# Circular_LED_v0_9b.net
KiCad netlist of a schematic drawn in EAGLE
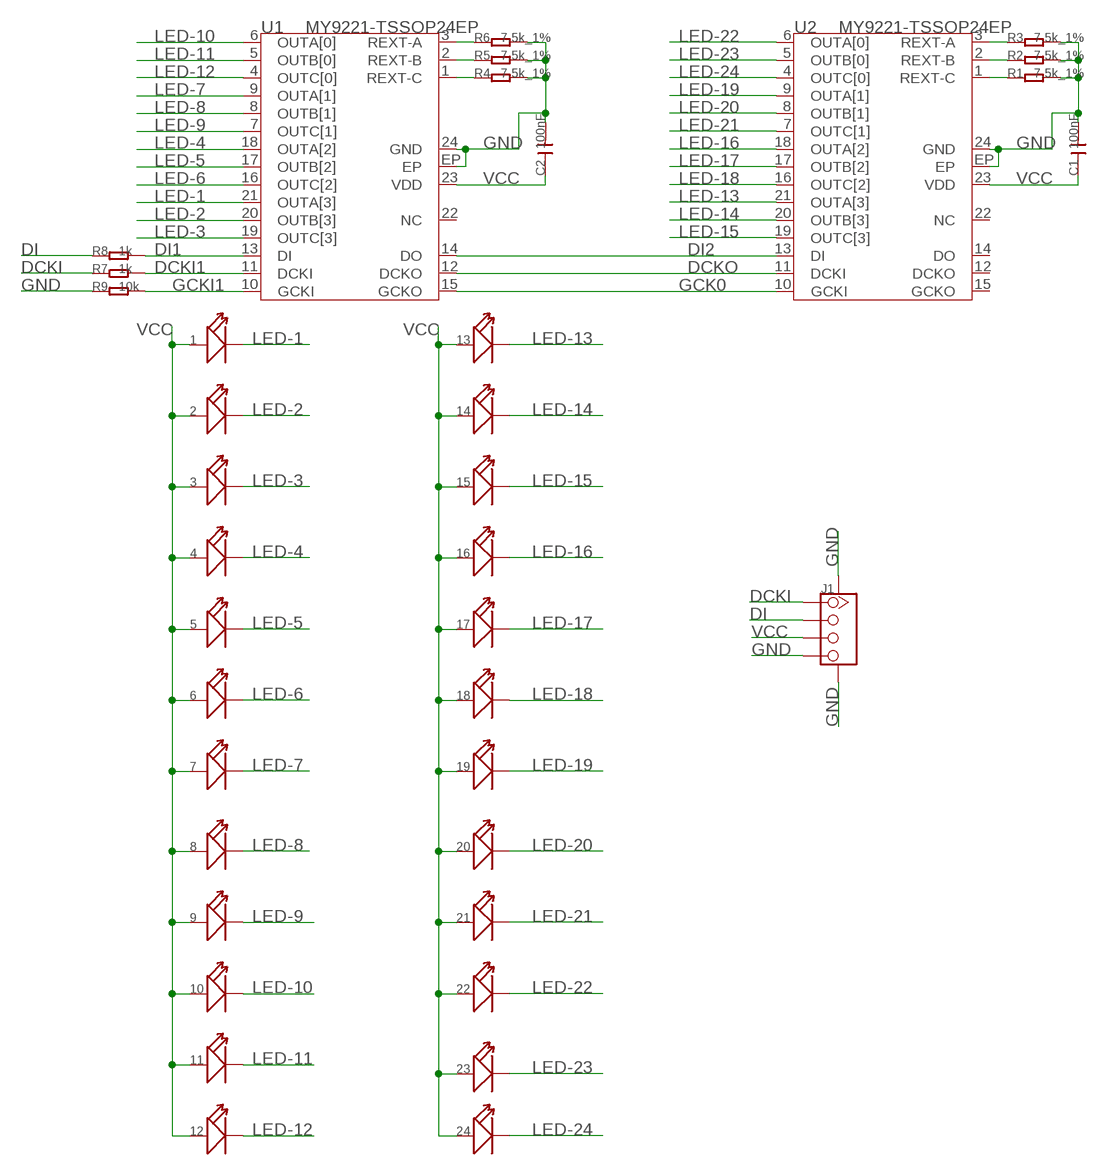
[diagram p0: schematic, sheet 1]

(export (version "E")
  (design (tool "Eeschema 10.0.6"))
  (components
    (comp (ref "1")
      (value "LED'1206'")
      (footprint "eagle-import:LED-1206")
      (libsource (lib "eagle-import") (part "LED'1206'"))
    )
    (comp (ref "2")
      (value "LED'1206'")
      (footprint "eagle-import:LED-1206")
      (libsource (lib "eagle-import") (part "LED'1206'"))
    )
    (comp (ref "3")
      (value "LED'1206'")
      (footprint "eagle-import:LED-1206")
      (libsource (lib "eagle-import") (part "LED'1206'"))
    )
    (comp (ref "4")
      (value "LED'1206'")
      (footprint "eagle-import:LED-1206")
      (libsource (lib "eagle-import") (part "LED'1206'"))
    )
    (comp (ref "5")
      (value "LED'1206'")
      (footprint "eagle-import:LED-1206")
      (libsource (lib "eagle-import") (part "LED'1206'"))
    )
    (comp (ref "6")
      (value "LED'1206'")
      (footprint "eagle-import:LED-1206")
      (libsource (lib "eagle-import") (part "LED'1206'"))
    )
    (comp (ref "7")
      (value "LED'1206'")
      (footprint "eagle-import:LED-1206")
      (libsource (lib "eagle-import") (part "LED'1206'"))
    )
    (comp (ref "8")
      (value "LED'1206'")
      (footprint "eagle-import:LED-1206")
      (libsource (lib "eagle-import") (part "LED'1206'"))
    )
    (comp (ref "9")
      (value "LED'1206'")
      (footprint "eagle-import:LED-1206")
      (libsource (lib "eagle-import") (part "LED'1206'"))
    )
    (comp (ref "10")
      (value "LED'1206'")
      (footprint "eagle-import:LED-1206")
      (libsource (lib "eagle-import") (part "LED'1206'"))
    )
    (comp (ref "11")
      (value "LED'1206'")
      (footprint "eagle-import:LED-1206")
      (libsource (lib "eagle-import") (part "LED'1206'"))
    )
    (comp (ref "12")
      (value "LED'1206'")
      (footprint "eagle-import:LED-1206")
      (libsource (lib "eagle-import") (part "LED'1206'"))
    )
    (comp (ref "13")
      (value "LED'1206'")
      (footprint "eagle-import:LED-1206")
      (libsource (lib "eagle-import") (part "LED'1206'"))
    )
    (comp (ref "14")
      (value "LED'1206'")
      (footprint "eagle-import:LED-1206")
      (libsource (lib "eagle-import") (part "LED'1206'"))
    )
    (comp (ref "15")
      (value "LED'1206'")
      (footprint "eagle-import:LED-1206")
      (libsource (lib "eagle-import") (part "LED'1206'"))
    )
    (comp (ref "16")
      (value "LED'1206'")
      (footprint "eagle-import:LED-1206")
      (libsource (lib "eagle-import") (part "LED'1206'"))
    )
    (comp (ref "17")
      (value "LED'1206'")
      (footprint "eagle-import:LED-1206")
      (libsource (lib "eagle-import") (part "LED'1206'"))
    )
    (comp (ref "18")
      (value "LED'1206'")
      (footprint "eagle-import:LED-1206")
      (libsource (lib "eagle-import") (part "LED'1206'"))
    )
    (comp (ref "19")
      (value "LED'1206'")
      (footprint "eagle-import:LED-1206")
      (libsource (lib "eagle-import") (part "LED'1206'"))
    )
    (comp (ref "20")
      (value "LED'1206'")
      (footprint "eagle-import:LED-1206")
      (libsource (lib "eagle-import") (part "LED'1206'"))
    )
    (comp (ref "21")
      (value "LED'1206'")
      (footprint "eagle-import:LED-1206")
      (libsource (lib "eagle-import") (part "LED'1206'"))
    )
    (comp (ref "22")
      (value "LED'1206'")
      (footprint "eagle-import:LED-1206")
      (libsource (lib "eagle-import") (part "LED'1206'"))
    )
    (comp (ref "23")
      (value "LED'1206'")
      (footprint "eagle-import:LED-1206")
      (libsource (lib "eagle-import") (part "LED'1206'"))
    )
    (comp (ref "24")
      (value "LED'1206'")
      (footprint "eagle-import:LED-1206")
      (libsource (lib "eagle-import") (part "LED'1206'"))
    )
    (comp (ref "C1")
      (value "100nF")
      (footprint "eagle-import:C0603")
      (libsource (lib "eagle-import") (part "C-0603"))
    )
    (comp (ref "C2")
      (value "100nF")
      (footprint "eagle-import:C0603")
      (libsource (lib "eagle-import") (part "C-0603"))
    )
    (comp (ref "J1")
      (value "TWIG-4P-2.0-SMD-FEMALE-REINFORCE'90D'")
      (footprint "eagle-import:4P-SMD-2.0-90D")
      (libsource (lib "eagle-import") (part "TWIG-4P-2.0-SMD-FEMALE-REINFORCE'90D'"))
    )
    (comp (ref "R1")
      (value "7.5k_1%")
      (footprint "eagle-import:R0603")
      (libsource (lib "eagle-import") (part "R-0603"))
    )
    (comp (ref "R2")
      (value "7.5k_1%")
      (footprint "eagle-import:R0603")
      (libsource (lib "eagle-import") (part "R-0603"))
    )
    (comp (ref "R3")
      (value "7.5k_1%")
      (footprint "eagle-import:R0603")
      (libsource (lib "eagle-import") (part "R-0603"))
    )
    (comp (ref "R4")
      (value "7.5k_1%")
      (footprint "eagle-import:R0603")
      (libsource (lib "eagle-import") (part "R-0603"))
    )
    (comp (ref "R5")
      (value "7.5k_1%")
      (footprint "eagle-import:R0603")
      (libsource (lib "eagle-import") (part "R-0603"))
    )
    (comp (ref "R6")
      (value "7.5k_1%")
      (footprint "eagle-import:R0603")
      (libsource (lib "eagle-import") (part "R-0603"))
    )
    (comp (ref "R7")
      (value "1k")
      (footprint "eagle-import:R0603")
      (libsource (lib "eagle-import") (part "R-0603"))
    )
    (comp (ref "R8")
      (value "1k")
      (footprint "eagle-import:R0603")
      (libsource (lib "eagle-import") (part "R-0603"))
    )
    (comp (ref "R9")
      (value "10k")
      (footprint "eagle-import:R0603")
      (libsource (lib "eagle-import") (part "R-0603"))
    )
    (comp (ref "U1")
      (value "MY9221-TSSOP24EP")
      (footprint "eagle-import:TSSOP24EP")
      (libsource (lib "eagle-import") (part "MY9221-TSSOP24EP"))
    )
    (comp (ref "U2")
      (value "MY9221-TSSOP24EP")
      (footprint "eagle-import:TSSOP24EP")
      (libsource (lib "eagle-import") (part "MY9221-TSSOP24EP"))
    )
  )
  (nets
    (net (code "1") (name "/DCKI") (class "Default")
      (node (ref "J1") (pin "1") (pinfunction "1_1") (pintype "bidirectional"))
      (node (ref "R7") (pin "1") (pinfunction "1_1") (pintype "passive"))
    )
    (net (code "2") (name "/DCKI1") (class "Default")
      (node (ref "R7") (pin "2") (pinfunction "2_2") (pintype "passive"))
      (node (ref "U1") (pin "11") (pinfunction "DCKI_11") (pintype "bidirectional"))
    )
    (net (code "3") (name "/DCKO") (class "Default")
      (node (ref "U1") (pin "12") (pinfunction "DCKO_12") (pintype "bidirectional"))
      (node (ref "U2") (pin "11") (pinfunction "DCKI_11") (pintype "bidirectional"))
    )
    (net (code "4") (name "/DI") (class "Default")
      (node (ref "J1") (pin "2") (pinfunction "2_2") (pintype "bidirectional"))
      (node (ref "R8") (pin "1") (pinfunction "1_1") (pintype "passive"))
    )
    (net (code "5") (name "/DI1") (class "Default")
      (node (ref "R8") (pin "2") (pinfunction "2_2") (pintype "passive"))
      (node (ref "U1") (pin "13") (pinfunction "DI_13") (pintype "bidirectional"))
    )
    (net (code "6") (name "/DI2") (class "Default")
      (node (ref "U1") (pin "14") (pinfunction "DO_14") (pintype "bidirectional"))
      (node (ref "U2") (pin "13") (pinfunction "DI_13") (pintype "bidirectional"))
    )
    (net (code "7") (name "/GCK0") (class "Default")
      (node (ref "U1") (pin "15") (pinfunction "GCKO_15") (pintype "bidirectional"))
      (node (ref "U2") (pin "10") (pinfunction "GCKI_10") (pintype "bidirectional"))
    )
    (net (code "8") (name "/GCKI1") (class "Default")
      (node (ref "R9") (pin "2") (pinfunction "2_2") (pintype "passive"))
      (node (ref "U1") (pin "10") (pinfunction "GCKI_10") (pintype "bidirectional"))
    )
    (net (code "9") (name "/GND") (class "Default")
      (node (ref "C1") (pin "2") (pinfunction "2_2") (pintype "passive"))
      (node (ref "C2") (pin "2") (pinfunction "2_2") (pintype "passive"))
      (node (ref "J1") (pin "4") (pinfunction "4_4") (pintype "bidirectional"))
      (node (ref "J1") (pin "SS1") (pinfunction "SS1_SS1") (pintype "bidirectional"))
      (node (ref "J1") (pin "SS2") (pinfunction "SS2_SS2") (pintype "bidirectional"))
      (node (ref "R1") (pin "2") (pinfunction "2_2") (pintype "passive"))
      (node (ref "R2") (pin "2") (pinfunction "2_2") (pintype "passive"))
      (node (ref "R3") (pin "2") (pinfunction "2_2") (pintype "passive"))
      (node (ref "R4") (pin "2") (pinfunction "2_2") (pintype "passive"))
      (node (ref "R5") (pin "2") (pinfunction "2_2") (pintype "passive"))
      (node (ref "R6") (pin "2") (pinfunction "2_2") (pintype "passive"))
      (node (ref "R9") (pin "1") (pinfunction "1_1") (pintype "passive"))
      (node (ref "U1") (pin "24") (pinfunction "GND_24") (pintype "power_in"))
      (node (ref "U1") (pin "EP") (pinfunction "EP_EP") (pintype "bidirectional"))
      (node (ref "U2") (pin "24") (pinfunction "GND_24") (pintype "power_in"))
      (node (ref "U2") (pin "EP") (pinfunction "EP_EP") (pintype "bidirectional"))
    )
    (net (code "10") (name "/LED-1") (class "Default")
      (node (ref "1") (pin "-") (pinfunction "-_-") (pintype "passive"))
      (node (ref "U1") (pin "21") (pinfunction "OUTA[3]_21") (pintype "bidirectional"))
    )
    (net (code "11") (name "/LED-2") (class "Default")
      (node (ref "2") (pin "-") (pinfunction "-_-") (pintype "passive"))
      (node (ref "U1") (pin "20") (pinfunction "OUTB[3]_20") (pintype "bidirectional"))
    )
    (net (code "12") (name "/LED-3") (class "Default")
      (node (ref "3") (pin "-") (pinfunction "-_-") (pintype "passive"))
      (node (ref "U1") (pin "19") (pinfunction "OUTC[3]_19") (pintype "bidirectional"))
    )
    (net (code "13") (name "/LED-4") (class "Default")
      (node (ref "4") (pin "-") (pinfunction "-_-") (pintype "passive"))
      (node (ref "U1") (pin "18") (pinfunction "OUTA[2]_18") (pintype "bidirectional"))
    )
    (net (code "14") (name "/LED-5") (class "Default")
      (node (ref "5") (pin "-") (pinfunction "-_-") (pintype "passive"))
      (node (ref "U1") (pin "17") (pinfunction "OUTB[2]_17") (pintype "bidirectional"))
    )
    (net (code "15") (name "/LED-6") (class "Default")
      (node (ref "6") (pin "-") (pinfunction "-_-") (pintype "passive"))
      (node (ref "U1") (pin "16") (pinfunction "OUTC[2]_16") (pintype "bidirectional"))
    )
    (net (code "16") (name "/LED-7") (class "Default")
      (node (ref "7") (pin "-") (pinfunction "-_-") (pintype "passive"))
      (node (ref "U1") (pin "9") (pinfunction "OUTA[1]_9") (pintype "bidirectional"))
    )
    (net (code "17") (name "/LED-8") (class "Default")
      (node (ref "8") (pin "-") (pinfunction "-_-") (pintype "passive"))
      (node (ref "U1") (pin "8") (pinfunction "OUTB[1]_8") (pintype "bidirectional"))
    )
    (net (code "18") (name "/LED-9") (class "Default")
      (node (ref "9") (pin "-") (pinfunction "-_-") (pintype "passive"))
      (node (ref "U1") (pin "7") (pinfunction "OUTC[1]_7") (pintype "bidirectional"))
    )
    (net (code "19") (name "/LED-10") (class "Default")
      (node (ref "10") (pin "-") (pinfunction "-_-") (pintype "passive"))
      (node (ref "U1") (pin "6") (pinfunction "OUTA[0]_6") (pintype "bidirectional"))
    )
    (net (code "20") (name "/LED-11") (class "Default")
      (node (ref "11") (pin "-") (pinfunction "-_-") (pintype "passive"))
      (node (ref "U1") (pin "5") (pinfunction "OUTB[0]_5") (pintype "bidirectional"))
    )
    (net (code "21") (name "/LED-12") (class "Default")
      (node (ref "12") (pin "-") (pinfunction "-_-") (pintype "passive"))
      (node (ref "U1") (pin "4") (pinfunction "OUTC[0]_4") (pintype "bidirectional"))
    )
    (net (code "22") (name "/LED-13") (class "Default")
      (node (ref "13") (pin "-") (pinfunction "-_-") (pintype "passive"))
      (node (ref "U2") (pin "21") (pinfunction "OUTA[3]_21") (pintype "bidirectional"))
    )
    (net (code "23") (name "/LED-14") (class "Default")
      (node (ref "14") (pin "-") (pinfunction "-_-") (pintype "passive"))
      (node (ref "U2") (pin "20") (pinfunction "OUTB[3]_20") (pintype "bidirectional"))
    )
    (net (code "24") (name "/LED-15") (class "Default")
      (node (ref "15") (pin "-") (pinfunction "-_-") (pintype "passive"))
      (node (ref "U2") (pin "19") (pinfunction "OUTC[3]_19") (pintype "bidirectional"))
    )
    (net (code "25") (name "/LED-16") (class "Default")
      (node (ref "16") (pin "-") (pinfunction "-_-") (pintype "passive"))
      (node (ref "U2") (pin "18") (pinfunction "OUTA[2]_18") (pintype "bidirectional"))
    )
    (net (code "26") (name "/LED-17") (class "Default")
      (node (ref "17") (pin "-") (pinfunction "-_-") (pintype "passive"))
      (node (ref "U2") (pin "17") (pinfunction "OUTB[2]_17") (pintype "bidirectional"))
    )
    (net (code "27") (name "/LED-18") (class "Default")
      (node (ref "18") (pin "-") (pinfunction "-_-") (pintype "passive"))
      (node (ref "U2") (pin "16") (pinfunction "OUTC[2]_16") (pintype "bidirectional"))
    )
    (net (code "28") (name "/LED-19") (class "Default")
      (node (ref "19") (pin "-") (pinfunction "-_-") (pintype "passive"))
      (node (ref "U2") (pin "9") (pinfunction "OUTA[1]_9") (pintype "bidirectional"))
    )
    (net (code "29") (name "/LED-20") (class "Default")
      (node (ref "20") (pin "-") (pinfunction "-_-") (pintype "passive"))
      (node (ref "U2") (pin "8") (pinfunction "OUTB[1]_8") (pintype "bidirectional"))
    )
    (net (code "30") (name "/LED-21") (class "Default")
      (node (ref "21") (pin "-") (pinfunction "-_-") (pintype "passive"))
      (node (ref "U2") (pin "7") (pinfunction "OUTC[1]_7") (pintype "bidirectional"))
    )
    (net (code "31") (name "/LED-22") (class "Default")
      (node (ref "22") (pin "-") (pinfunction "-_-") (pintype "passive"))
      (node (ref "U2") (pin "6") (pinfunction "OUTA[0]_6") (pintype "bidirectional"))
    )
    (net (code "32") (name "/LED-23") (class "Default")
      (node (ref "23") (pin "-") (pinfunction "-_-") (pintype "passive"))
      (node (ref "U2") (pin "5") (pinfunction "OUTB[0]_5") (pintype "bidirectional"))
    )
    (net (code "33") (name "/LED-24") (class "Default")
      (node (ref "24") (pin "-") (pinfunction "-_-") (pintype "passive"))
      (node (ref "U2") (pin "4") (pinfunction "OUTC[0]_4") (pintype "bidirectional"))
    )
    (net (code "34") (name "/VCC") (class "Default")
      (node (ref "1") (pin "+") (pinfunction "+_+") (pintype "passive"))
      (node (ref "10") (pin "+") (pinfunction "+_+") (pintype "passive"))
      (node (ref "11") (pin "+") (pinfunction "+_+") (pintype "passive"))
      (node (ref "12") (pin "+") (pinfunction "+_+") (pintype "passive"))
      (node (ref "13") (pin "+") (pinfunction "+_+") (pintype "passive"))
      (node (ref "14") (pin "+") (pinfunction "+_+") (pintype "passive"))
      (node (ref "15") (pin "+") (pinfunction "+_+") (pintype "passive"))
      (node (ref "16") (pin "+") (pinfunction "+_+") (pintype "passive"))
      (node (ref "17") (pin "+") (pinfunction "+_+") (pintype "passive"))
      (node (ref "18") (pin "+") (pinfunction "+_+") (pintype "passive"))
      (node (ref "19") (pin "+") (pinfunction "+_+") (pintype "passive"))
      (node (ref "2") (pin "+") (pinfunction "+_+") (pintype "passive"))
      (node (ref "20") (pin "+") (pinfunction "+_+") (pintype "passive"))
      (node (ref "21") (pin "+") (pinfunction "+_+") (pintype "passive"))
      (node (ref "22") (pin "+") (pinfunction "+_+") (pintype "passive"))
      (node (ref "23") (pin "+") (pinfunction "+_+") (pintype "passive"))
      (node (ref "24") (pin "+") (pinfunction "+_+") (pintype "passive"))
      (node (ref "3") (pin "+") (pinfunction "+_+") (pintype "passive"))
      (node (ref "4") (pin "+") (pinfunction "+_+") (pintype "passive"))
      (node (ref "5") (pin "+") (pinfunction "+_+") (pintype "passive"))
      (node (ref "6") (pin "+") (pinfunction "+_+") (pintype "passive"))
      (node (ref "7") (pin "+") (pinfunction "+_+") (pintype "passive"))
      (node (ref "8") (pin "+") (pinfunction "+_+") (pintype "passive"))
      (node (ref "9") (pin "+") (pinfunction "+_+") (pintype "passive"))
      (node (ref "C1") (pin "1") (pinfunction "1_1") (pintype "passive"))
      (node (ref "C2") (pin "1") (pinfunction "1_1") (pintype "passive"))
      (node (ref "J1") (pin "3") (pinfunction "3_3") (pintype "bidirectional"))
      (node (ref "U1") (pin "23") (pinfunction "VDD_23") (pintype "power_in"))
      (node (ref "U2") (pin "23") (pinfunction "VDD_23") (pintype "power_in"))
    )
    (net (code "35") (name "Net-(U1-REXT-A)") (class "Default")
      (node (ref "R6") (pin "1") (pinfunction "1_1") (pintype "passive"))
      (node (ref "U1") (pin "3") (pinfunction "REXT-A_3") (pintype "bidirectional"))
    )
    (net (code "36") (name "Net-(U1-REXT-B)") (class "Default")
      (node (ref "R5") (pin "1") (pinfunction "1_1") (pintype "passive"))
      (node (ref "U1") (pin "2") (pinfunction "REXT-B_2") (pintype "bidirectional"))
    )
    (net (code "37") (name "Net-(U1-REXT-C)") (class "Default")
      (node (ref "R4") (pin "1") (pinfunction "1_1") (pintype "passive"))
      (node (ref "U1") (pin "1") (pinfunction "REXT-C_1") (pintype "bidirectional"))
    )
    (net (code "38") (name "Net-(U2-REXT-A)") (class "Default")
      (node (ref "R3") (pin "1") (pinfunction "1_1") (pintype "passive"))
      (node (ref "U2") (pin "3") (pinfunction "REXT-A_3") (pintype "bidirectional"))
    )
    (net (code "39") (name "Net-(U2-REXT-B)") (class "Default")
      (node (ref "R2") (pin "1") (pinfunction "1_1") (pintype "passive"))
      (node (ref "U2") (pin "2") (pinfunction "REXT-B_2") (pintype "bidirectional"))
    )
    (net (code "40") (name "Net-(U2-REXT-C)") (class "Default")
      (node (ref "R1") (pin "1") (pinfunction "1_1") (pintype "passive"))
      (node (ref "U2") (pin "1") (pinfunction "REXT-C_1") (pintype "bidirectional"))
    )
    (net (code "41") (name "unconnected-(U1-NC-Pad22)") (class "Default")
      (node (ref "U1") (pin "22") (pinfunction "NC_22") (pintype "bidirectional"))
    )
    (net (code "42") (name "unconnected-(U2-DCKO-Pad12)") (class "Default")
      (node (ref "U2") (pin "12") (pinfunction "DCKO_12") (pintype "bidirectional"))
    )
    (net (code "43") (name "unconnected-(U2-DO-Pad14)") (class "Default")
      (node (ref "U2") (pin "14") (pinfunction "DO_14") (pintype "bidirectional"))
    )
    (net (code "44") (name "unconnected-(U2-GCKO-Pad15)") (class "Default")
      (node (ref "U2") (pin "15") (pinfunction "GCKO_15") (pintype "bidirectional"))
    )
    (net (code "45") (name "unconnected-(U2-NC-Pad22)") (class "Default")
      (node (ref "U2") (pin "22") (pinfunction "NC_22") (pintype "bidirectional"))
    )
  )
)
